# LED_Series.net
KiCad netlist of a schematic drawn in EAGLE
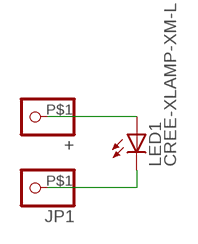
[diagram p0: schematic, sheet 1]

(export (version "E")
  (design (tool "Eeschema 10.0.6"))
  (components
    (comp (ref "+")
      (value "PINHD-1X1")
      (footprint "eagle-import:1X01")
      (libsource (lib "eagle-import") (part "PINHD-1X1"))
    )
    (comp (ref "JP1")
      (value "PINHD-1X1")
      (footprint "eagle-import:1X01")
      (libsource (lib "eagle-import") (part "PINHD-1X1"))
    )
    (comp (ref "LED1")
      (value "CREE-XLAMP-XM-L")
      (footprint "eagle-import:CREE-XLAMP-XM-L")
      (libsource (lib "eagle-import") (part "CREE-XLAMP-XM-L"))
    )
  )
  (nets
    (net (code "1") (name "Net-(+-1)") (class "Default")
      (node (ref "+") (pin "P$1") (pinfunction "1_P$1") (pintype "passive"))
      (node (ref "LED1") (pin "A") (pinfunction "A_A") (pintype "passive"))
      (node (ref "LED1") (pin "A@1") (pinfunction "A_A@1") (pintype "passive"))
    )
    (net (code "2") (name "Net-(JP1-1)") (class "Default")
      (node (ref "JP1") (pin "P$1") (pinfunction "1_P$1") (pintype "passive"))
      (node (ref "LED1") (pin "C") (pinfunction "C_C") (pintype "passive"))
      (node (ref "LED1") (pin "C@1") (pinfunction "C_C@1") (pintype "passive"))
    )
  )
)
